# QCopterFC_EXT_Sch.net
KiCad netlist of a schematic drawn in Altium Designer
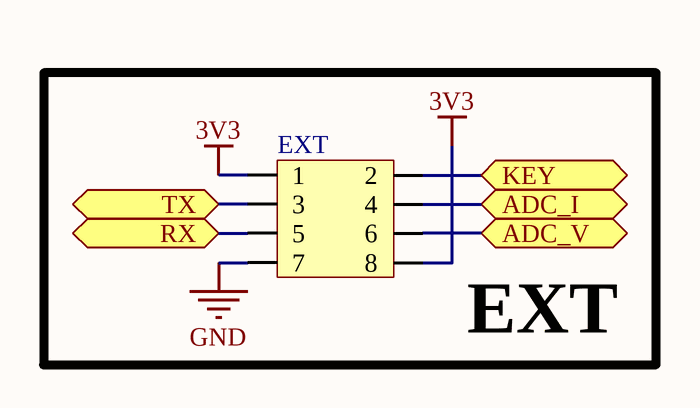
[diagram p0: QCopterFC_EXT_Sch.SchDoc]

(export (version "E")
  (design (tool "Eeschema 10.0.6"))
  (components
    (comp (ref "EXT")
      (value "HDR2X4_90_2.54")
      (footprint "PCB_Connector:HDR2X4_90_2.54")
      (description "Header")
      (libsource (lib "SCH_Connector") (part "HDR2X4_90_2.54"))
    )
  )
  (nets
    (net (code "1") (name "/ADC_I") (class "Default")
      (node (ref "EXT") (pin "4") (pinfunction "4_4") (pintype "passive"))
    )
    (net (code "2") (name "/ADC_V") (class "Default")
      (node (ref "EXT") (pin "6") (pinfunction "6_6") (pintype "passive"))
    )
    (net (code "4") (name "/KEY") (class "Default")
      (node (ref "EXT") (pin "2") (pinfunction "2_2") (pintype "passive"))
    )
    (net (code "5") (name "/RX") (class "Default")
      (node (ref "EXT") (pin "5") (pinfunction "5_5") (pintype "passive"))
    )
    (net (code "6") (name "/TX") (class "Default")
      (node (ref "EXT") (pin "3") (pinfunction "3_3") (pintype "passive"))
    )
    (net (code "7") (name "3V3") (class "Default")
      (node (ref "EXT") (pin "1") (pinfunction "1_1") (pintype "passive"))
      (node (ref "EXT") (pin "8") (pinfunction "8_8") (pintype "passive"))
    )
    (net (code "8") (name "GND") (class "Default")
      (node (ref "EXT") (pin "7") (pinfunction "7_7") (pintype "passive"))
    )
  )
)
